# CH32L103F8U6-R0.net
KiCad netlist of a schematic drawn in Altium Designer
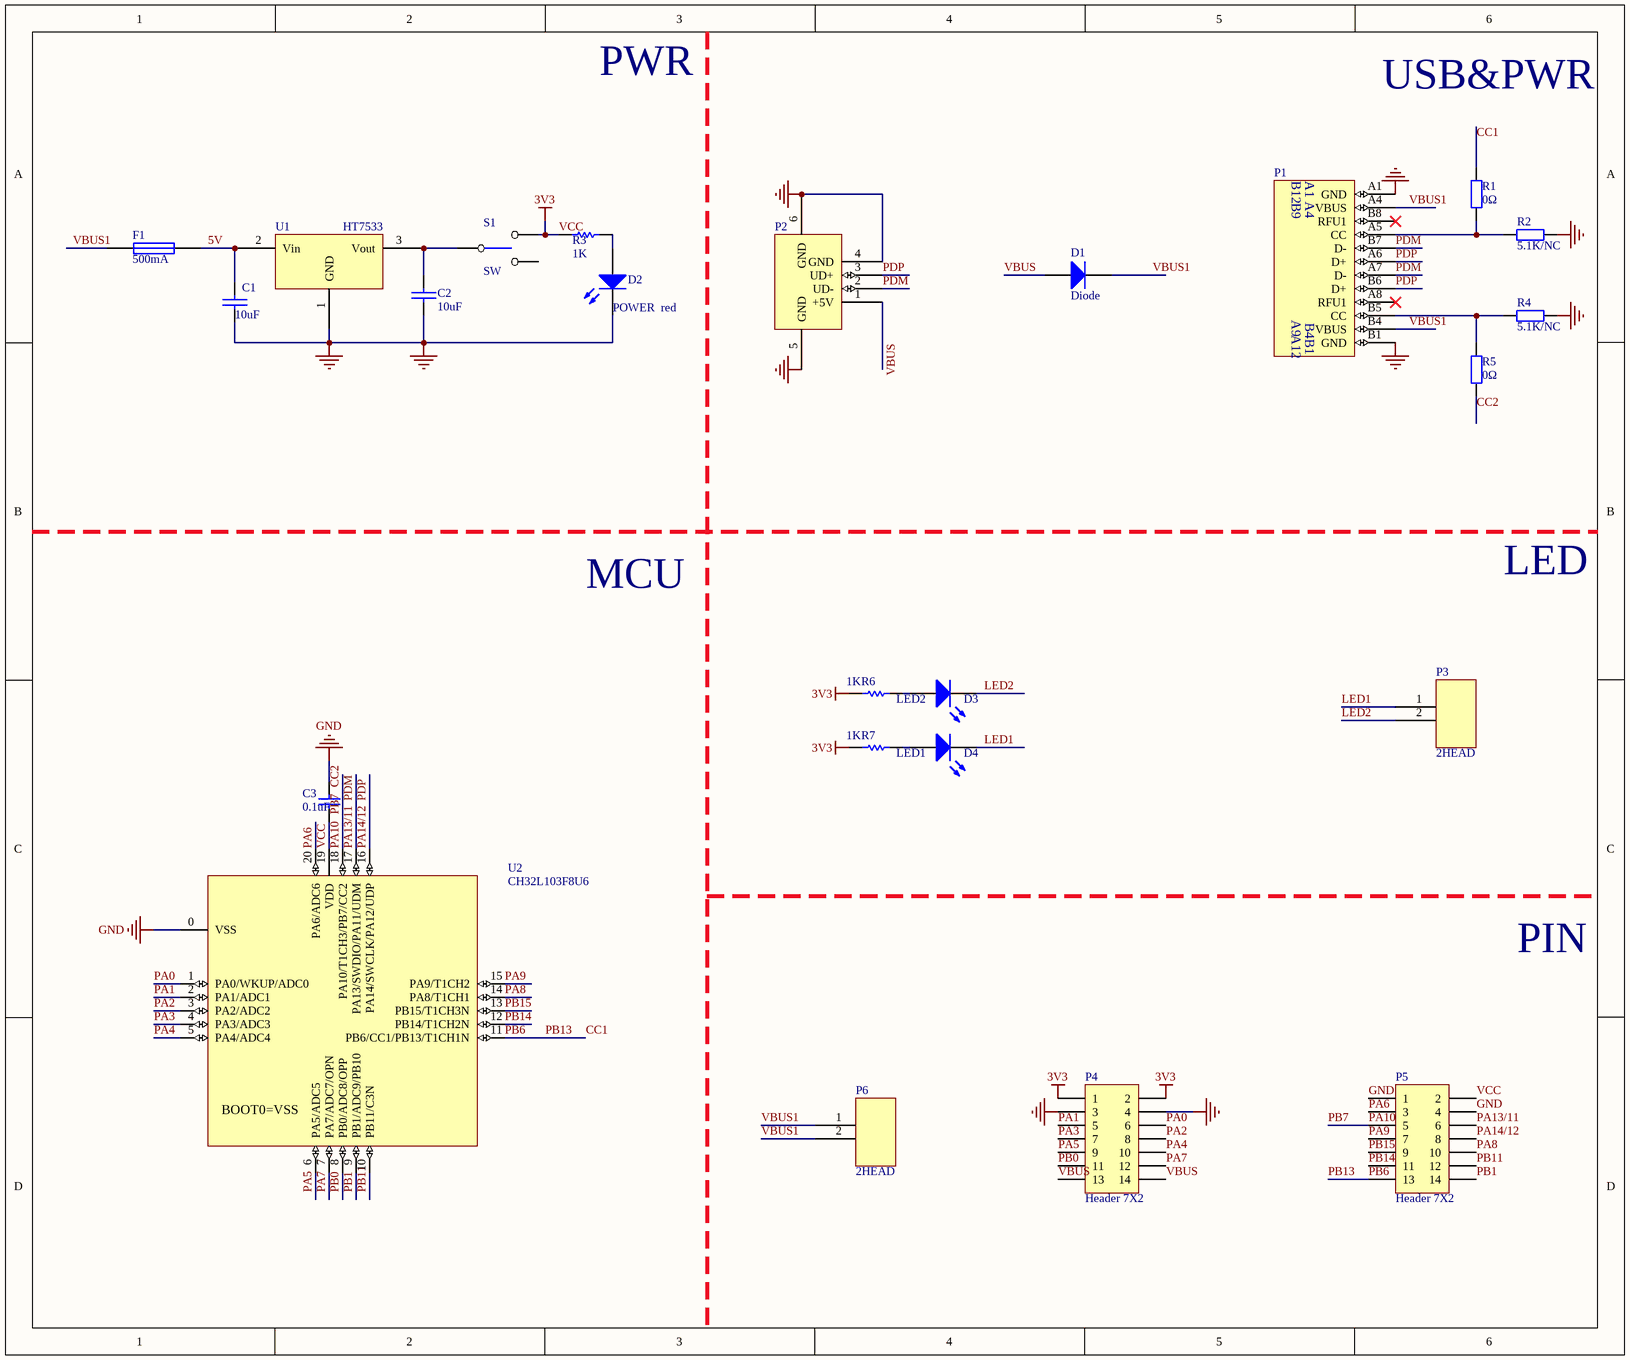
[diagram p0: CH32L103F8U6-R0.SchDoc]

(export (version "E")
  (design (tool "Eeschema 10.0.6"))
  (components
    (comp (ref "C1")
      (value "10uF")
      (footprint "0603_C")
      (description "Capacitor")
      (libsource (lib "*") (part "CAP"))
    )
    (comp (ref "C2")
      (value "10uF")
      (footprint "0603_C")
      (description "Capacitor")
      (libsource (lib "*") (part "CAP"))
    )
    (comp (ref "C3")
      (value "0.1uF")
      (footprint "0603_C")
      (description "Capacitor")
      (fields (field (name "PUBLISHER") "Altium Limited"))
      (libsource (lib "*") (part "Cap"))
    )
    (comp (ref "D1")
      (value "Diode")
      (footprint "SOD-123")
      (description "Default Diode")
      (fields (field (name "PUBLISHER") "Altium Limited"))
      (libsource (lib "Miscellaneous Devices") (part "Diode"))
    )
    (comp (ref "D2")
      (value "POWER  red")
      (footprint "0603+")
      (description "Typical INFRARED GaAs LED")
      (fields (field (name "PUBLISHER") "Altium Limited"))
      (libsource (lib "*") (part "LED0"))
    )
    (comp (ref "D3")
      (value "LED2")
      (footprint "0603+")
      (description "Typical INFRARED GaAs LED")
      (fields (field (name "PUBLISHER") "Altium Limited"))
      (libsource (lib "*") (part "LED0"))
    )
    (comp (ref "D4")
      (value "LED1")
      (footprint "0603+")
      (description "Typical INFRARED GaAs LED")
      (fields (field (name "PUBLISHER") "Altium Limited"))
      (libsource (lib "*") (part "LED0"))
    )
    (comp (ref "F1")
      (value "500mA")
      (footprint "0603")
      (description "Fuse")
      (libsource (lib "*") (part "FUSE1"))
    )
    (comp (ref "P1")
      (value "TYPE-C")
      (footprint "TYPE-C-Receptacle-2.0")
      (libsource (lib "*") (part "TYPE-C1"))
    )
    (comp (ref "P2")
      (value "USB_A")
      (footprint "USBAF")
      (description "USB Port")
      (libsource (lib "*") (part "USB"))
    )
    (comp (ref "P3") (value "2HEAD") (footprint "SIP2-2.54mm") (libsource (lib "*") (part "2HEAD")))
    (comp (ref "P4")
      (value "Header 7X2")
      (footprint "IDC14-2.54mm")
      (description "Header, 7-Pin, Dual row")
      (fields (field (name "PUBLISHER") "Altium Limited"))
      (libsource (lib "Miscellaneous Connectors") (part "Header 7X2"))
    )
    (comp (ref "P5")
      (value "Header 7X2")
      (footprint "IDC14-2.54mm")
      (description "Header, 7-Pin, Dual row")
      (fields (field (name "PUBLISHER") "Altium Limited"))
      (libsource (lib "Miscellaneous Connectors") (part "Header 7X2"))
    )
    (comp (ref "P6") (value "2HEAD") (footprint "SIP2-2.54mm") (libsource (lib "*") (part "2HEAD")))
    (comp (ref "R1")
      (value "0Ω")
      (footprint "0603")
      (description "Resistor")
      (libsource (lib "") (part "Res2_1"))
    )
    (comp (ref "R2")
      (value "5.1K/NC")
      (footprint "0603")
      (description "Resistor")
      (libsource (lib "Miscellaneous Devices") (part "Res2"))
    )
    (comp (ref "R3")
      (value "1K")
      (footprint "0603")
      (description "Semiconductor Resistor")
      (libsource (lib "*") (part "Res Semi"))
    )
    (comp (ref "R4")
      (value "5.1K/NC")
      (footprint "0603")
      (description "Resistor")
      (libsource (lib "Miscellaneous Devices") (part "Res2"))
    )
    (comp (ref "R5")
      (value "0Ω")
      (footprint "0603")
      (description "Resistor")
      (libsource (lib "") (part "Res2_1"))
    )
    (comp (ref "R6")
      (value "1K")
      (footprint "0603")
      (description "Semiconductor Resistor")
      (libsource (lib "*") (part "Res Semi"))
    )
    (comp (ref "R7")
      (value "1K")
      (footprint "0603")
      (description "Semiconductor Resistor")
      (libsource (lib "*") (part "Res Semi"))
    )
    (comp (ref "S1") (value "SW") (footprint "SW1") (libsource (lib "*") (part "SW")))
    (comp (ref "U1")
      (value "HT7533")
      (footprint "SOT-89")
      (libsource (lib "wch_sch_others") (part "1117-3.3V"))
    )
    (comp (ref "U2")
      (value "CH32L103F8U6")
      (footprint "QFN20_3X3")
      (description "RISC-V LMD-MCU, 96MHz, USB, Type-C/PD-5K1, CAN, OPA, lower power, for motor")
      (libsource (lib "CHXXX") (part "CH32L103F8U6"))
    )
  )
  (nets
    (net (code "1") (name "/5V") (class "Default")
      (node (ref "C1") (pin "1") (pinfunction "1_1") (pintype "passive"))
      (node (ref "F1") (pin "2") (pinfunction "2_2") (pintype "passive"))
      (node (ref "U1") (pin "2") (pinfunction "Vin_2") (pintype "passive"))
    )
    (net (code "3") (name "/CC1") (class "Default")
      (node (ref "P5") (pin "13") (pinfunction "13_13") (pintype "passive"))
      (node (ref "R1") (pin "2") (pinfunction "2_2") (pintype "passive"))
      (node (ref "U2") (pin "11") (pinfunction "PB6/CC1/PB13/T1CH1N_11") (pintype "bidirectional"))
    )
    (net (code "4") (name "/CC2") (class "Default")
      (node (ref "P5") (pin "5") (pinfunction "5_5") (pintype "passive"))
      (node (ref "R5") (pin "1") (pinfunction "1_1") (pintype "passive"))
      (node (ref "U2") (pin "18") (pinfunction "PA10/T1CH3/PB7/CC2_18") (pintype "bidirectional"))
    )
    (net (code "5") (name "/LED1") (class "Default")
      (node (ref "D4") (pin "2") (pinfunction "K_2") (pintype "passive"))
      (node (ref "P3") (pin "1") (pintype "passive"))
    )
    (net (code "6") (name "/LED2") (class "Default")
      (node (ref "D3") (pin "2") (pinfunction "K_2") (pintype "passive"))
      (node (ref "P3") (pin "2") (pintype "passive"))
    )
    (net (code "7") (name "/PA0") (class "Default")
      (node (ref "P4") (pin "6") (pinfunction "6_6") (pintype "passive"))
      (node (ref "U2") (pin "1") (pinfunction "PA0/WKUP/ADC0_1") (pintype "bidirectional"))
    )
    (net (code "8") (name "/PA1") (class "Default")
      (node (ref "P4") (pin "5") (pinfunction "5_5") (pintype "passive"))
      (node (ref "U2") (pin "2") (pinfunction "PA1/ADC1_2") (pintype "bidirectional"))
    )
    (net (code "9") (name "/PA2") (class "Default")
      (node (ref "P4") (pin "8") (pinfunction "8_8") (pintype "passive"))
      (node (ref "U2") (pin "3") (pinfunction "PA2/ADC2_3") (pintype "bidirectional"))
    )
    (net (code "10") (name "/PA3") (class "Default")
      (node (ref "P4") (pin "7") (pinfunction "7_7") (pintype "passive"))
      (node (ref "U2") (pin "4") (pinfunction "PA3/ADC3_4") (pintype "bidirectional"))
    )
    (net (code "11") (name "/PA4") (class "Default")
      (node (ref "P4") (pin "10") (pinfunction "10_10") (pintype "passive"))
      (node (ref "U2") (pin "5") (pinfunction "PA4/ADC4_5") (pintype "bidirectional"))
    )
    (net (code "12") (name "/PA5") (class "Default")
      (node (ref "P4") (pin "9") (pinfunction "9_9") (pintype "passive"))
      (node (ref "U2") (pin "6") (pinfunction "PA5/ADC5_6") (pintype "bidirectional"))
    )
    (net (code "13") (name "/PA6") (class "Default")
      (node (ref "P5") (pin "3") (pinfunction "3_3") (pintype "passive"))
      (node (ref "U2") (pin "20") (pinfunction "PA6/ADC6_20") (pintype "bidirectional"))
    )
    (net (code "14") (name "/PA7") (class "Default")
      (node (ref "P4") (pin "12") (pinfunction "12_12") (pintype "passive"))
      (node (ref "U2") (pin "7") (pinfunction "PA7/ADC7/OPN_7") (pintype "bidirectional"))
    )
    (net (code "15") (name "/PA8") (class "Default")
      (node (ref "P5") (pin "10") (pinfunction "10_10") (pintype "passive"))
      (node (ref "U2") (pin "14") (pinfunction "PA8/T1CH1_14") (pintype "bidirectional"))
    )
    (net (code "16") (name "/PA9") (class "Default")
      (node (ref "P5") (pin "7") (pinfunction "7_7") (pintype "passive"))
      (node (ref "U2") (pin "15") (pinfunction "PA9/T1CH2_15") (pintype "bidirectional"))
    )
    (net (code "17") (name "/PA13{slash}11") (class "Default")
      (node (ref "P1") (pin "A7") (pinfunction "D-_A7") (pintype "bidirectional"))
      (node (ref "P1") (pin "B7") (pinfunction "D-_B7") (pintype "bidirectional"))
      (node (ref "P2") (pin "2") (pinfunction "UD-_2") (pintype "bidirectional"))
      (node (ref "P5") (pin "6") (pinfunction "6_6") (pintype "passive"))
      (node (ref "U2") (pin "17") (pinfunction "PA13/SWDIO/PA11/UDM_17") (pintype "bidirectional"))
    )
    (net (code "18") (name "/PA14{slash}12") (class "Default")
      (node (ref "P1") (pin "A6") (pinfunction "D+_A6") (pintype "bidirectional"))
      (node (ref "P1") (pin "B6") (pinfunction "D+_B6") (pintype "bidirectional"))
      (node (ref "P2") (pin "3") (pinfunction "UD+_3") (pintype "bidirectional"))
      (node (ref "P5") (pin "8") (pinfunction "8_8") (pintype "passive"))
      (node (ref "U2") (pin "16") (pinfunction "PA14/SWCLK/PA12/UDP_16") (pintype "bidirectional"))
    )
    (net (code "19") (name "/PB0") (class "Default")
      (node (ref "P4") (pin "11") (pinfunction "11_11") (pintype "passive"))
      (node (ref "U2") (pin "8") (pinfunction "PB0/ADC8/OPP_8") (pintype "bidirectional"))
    )
    (net (code "20") (name "/PB1") (class "Default")
      (node (ref "P5") (pin "14") (pinfunction "14_14") (pintype "passive"))
      (node (ref "U2") (pin "9") (pinfunction "PB1/ADC9/PB10_9") (pintype "bidirectional"))
    )
    (net (code "21") (name "/PB11") (class "Default")
      (node (ref "P5") (pin "12") (pinfunction "12_12") (pintype "passive"))
      (node (ref "U2") (pin "10") (pinfunction "PB11/C3N_10") (pintype "bidirectional"))
    )
    (net (code "22") (name "/PB14") (class "Default")
      (node (ref "P5") (pin "11") (pinfunction "11_11") (pintype "passive"))
      (node (ref "U2") (pin "12") (pinfunction "PB14/T1CH2N_12") (pintype "bidirectional"))
    )
    (net (code "23") (name "/PB15") (class "Default")
      (node (ref "P5") (pin "9") (pinfunction "9_9") (pintype "passive"))
      (node (ref "U2") (pin "13") (pinfunction "PB15/T1CH3N_13") (pintype "bidirectional"))
    )
    (net (code "24") (name "/VBUS") (class "Default")
      (node (ref "D1") (pin "1") (pinfunction "A_1") (pintype "passive"))
      (node (ref "P2") (pin "1") (pinfunction "+5V_1") (pintype "power_in"))
      (node (ref "P4") (pin "13") (pinfunction "13_13") (pintype "passive"))
      (node (ref "P4") (pin "14") (pinfunction "14_14") (pintype "passive"))
    )
    (net (code "25") (name "/VBUS1") (class "Default")
      (node (ref "D1") (pin "2") (pinfunction "K_2") (pintype "passive"))
      (node (ref "F1") (pin "1") (pinfunction "1_1") (pintype "passive"))
      (node (ref "P1") (pin "A4") (pinfunction "VBUS_A4") (pintype "bidirectional"))
      (node (ref "P1") (pin "B4") (pinfunction "VBUS_B4") (pintype "bidirectional"))
      (node (ref "P6") (pin "1") (pintype "passive"))
      (node (ref "P6") (pin "2") (pintype "passive"))
    )
    (net (code "26") (name "3V3") (class "Default")
      (node (ref "C3") (pin "1") (pinfunction "1_1") (pintype "passive"))
      (node (ref "P4") (pin "1") (pinfunction "1_1") (pintype "passive"))
      (node (ref "P4") (pin "2") (pinfunction "2_2") (pintype "passive"))
      (node (ref "P5") (pin "2") (pinfunction "2_2") (pintype "passive"))
      (node (ref "R3") (pin "2") (pinfunction "2_2") (pintype "passive"))
      (node (ref "R6") (pin "1") (pinfunction "1_1") (pintype "passive"))
      (node (ref "R7") (pin "1") (pinfunction "1_1") (pintype "passive"))
      (node (ref "S1") (pin "3") (pinfunction "3_3") (pintype "passive"))
      (node (ref "U2") (pin "19") (pinfunction "VDD_19") (pintype "power_in"))
    )
    (net (code "27") (name "GND") (class "Default")
      (node (ref "C1") (pin "2") (pinfunction "2_2") (pintype "passive"))
      (node (ref "C2") (pin "2") (pinfunction "2_2") (pintype "passive"))
      (node (ref "C3") (pin "2") (pinfunction "2_2") (pintype "passive"))
      (node (ref "D2") (pin "2") (pinfunction "K_2") (pintype "passive"))
      (node (ref "P1") (pin "A1") (pinfunction "GND_A1") (pintype "bidirectional"))
      (node (ref "P1") (pin "B1") (pinfunction "GND_B1") (pintype "bidirectional"))
      (node (ref "P2") (pin "4") (pinfunction "GND_4") (pintype "power_in"))
      (node (ref "P2") (pin "5") (pinfunction "GND_5") (pintype "power_in"))
      (node (ref "P2") (pin "6") (pinfunction "GND_6") (pintype "power_in"))
      (node (ref "P4") (pin "3") (pinfunction "3_3") (pintype "passive"))
      (node (ref "P4") (pin "4") (pinfunction "4_4") (pintype "passive"))
      (node (ref "P5") (pin "1") (pinfunction "1_1") (pintype "passive"))
      (node (ref "P5") (pin "4") (pinfunction "4_4") (pintype "passive"))
      (node (ref "R2") (pin "2") (pinfunction "2_2") (pintype "passive"))
      (node (ref "R4") (pin "2") (pinfunction "2_2") (pintype "passive"))
      (node (ref "U1") (pin "1") (pinfunction "GND_1") (pintype "passive"))
      (node (ref "U2") (pin "0") (pinfunction "VSS_0") (pintype "power_in"))
    )
    (net (code "28") (name "Net-(D2-A)") (class "Default")
      (node (ref "D2") (pin "1") (pinfunction "A_1") (pintype "passive"))
      (node (ref "R3") (pin "1") (pinfunction "1_1") (pintype "passive"))
    )
    (net (code "29") (name "Net-(D3-A)") (class "Default")
      (node (ref "D3") (pin "1") (pinfunction "A_1") (pintype "passive"))
      (node (ref "R6") (pin "2") (pinfunction "2_2") (pintype "passive"))
    )
    (net (code "30") (name "Net-(D4-A)") (class "Default")
      (node (ref "D4") (pin "1") (pinfunction "A_1") (pintype "passive"))
      (node (ref "R7") (pin "2") (pinfunction "2_2") (pintype "passive"))
    )
    (net (code "31") (name "Net-(P1-CC-PadA5)") (class "Default")
      (node (ref "P1") (pin "A5") (pinfunction "CC_A5") (pintype "bidirectional"))
      (node (ref "R1") (pin "1") (pinfunction "1_1") (pintype "passive"))
      (node (ref "R2") (pin "1") (pinfunction "1_1") (pintype "passive"))
    )
    (net (code "32") (name "Net-(P1-CC-PadB5)") (class "Default")
      (node (ref "P1") (pin "B5") (pinfunction "CC_B5") (pintype "bidirectional"))
      (node (ref "R4") (pin "1") (pinfunction "1_1") (pintype "passive"))
      (node (ref "R5") (pin "2") (pinfunction "2_2") (pintype "passive"))
    )
    (net (code "33") (name "Net-(U1-Vout)") (class "Default")
      (node (ref "C2") (pin "1") (pinfunction "1_1") (pintype "passive"))
      (node (ref "S1") (pin "1") (pinfunction "1_1") (pintype "passive"))
      (node (ref "U1") (pin "3") (pinfunction "Vout_3") (pintype "passive"))
    )
    (net (code "34") (name "unconnected-(P1-RFU1-PadA8)") (class "Default")
      (node (ref "P1") (pin "A8") (pinfunction "RFU1_A8") (pintype "bidirectional+no_connect"))
    )
    (net (code "35") (name "unconnected-(P1-RFU1-PadB8)") (class "Default")
      (node (ref "P1") (pin "B8") (pinfunction "RFU1_B8") (pintype "bidirectional+no_connect"))
    )
    (net (code "36") (name "unconnected-(S1-Pad2)") (class "Default")
      (node (ref "S1") (pin "2") (pinfunction "2_2") (pintype "passive"))
    )
  )
)
